# vc8.net
KiCad netlist of a schematic drawn in EAGLE
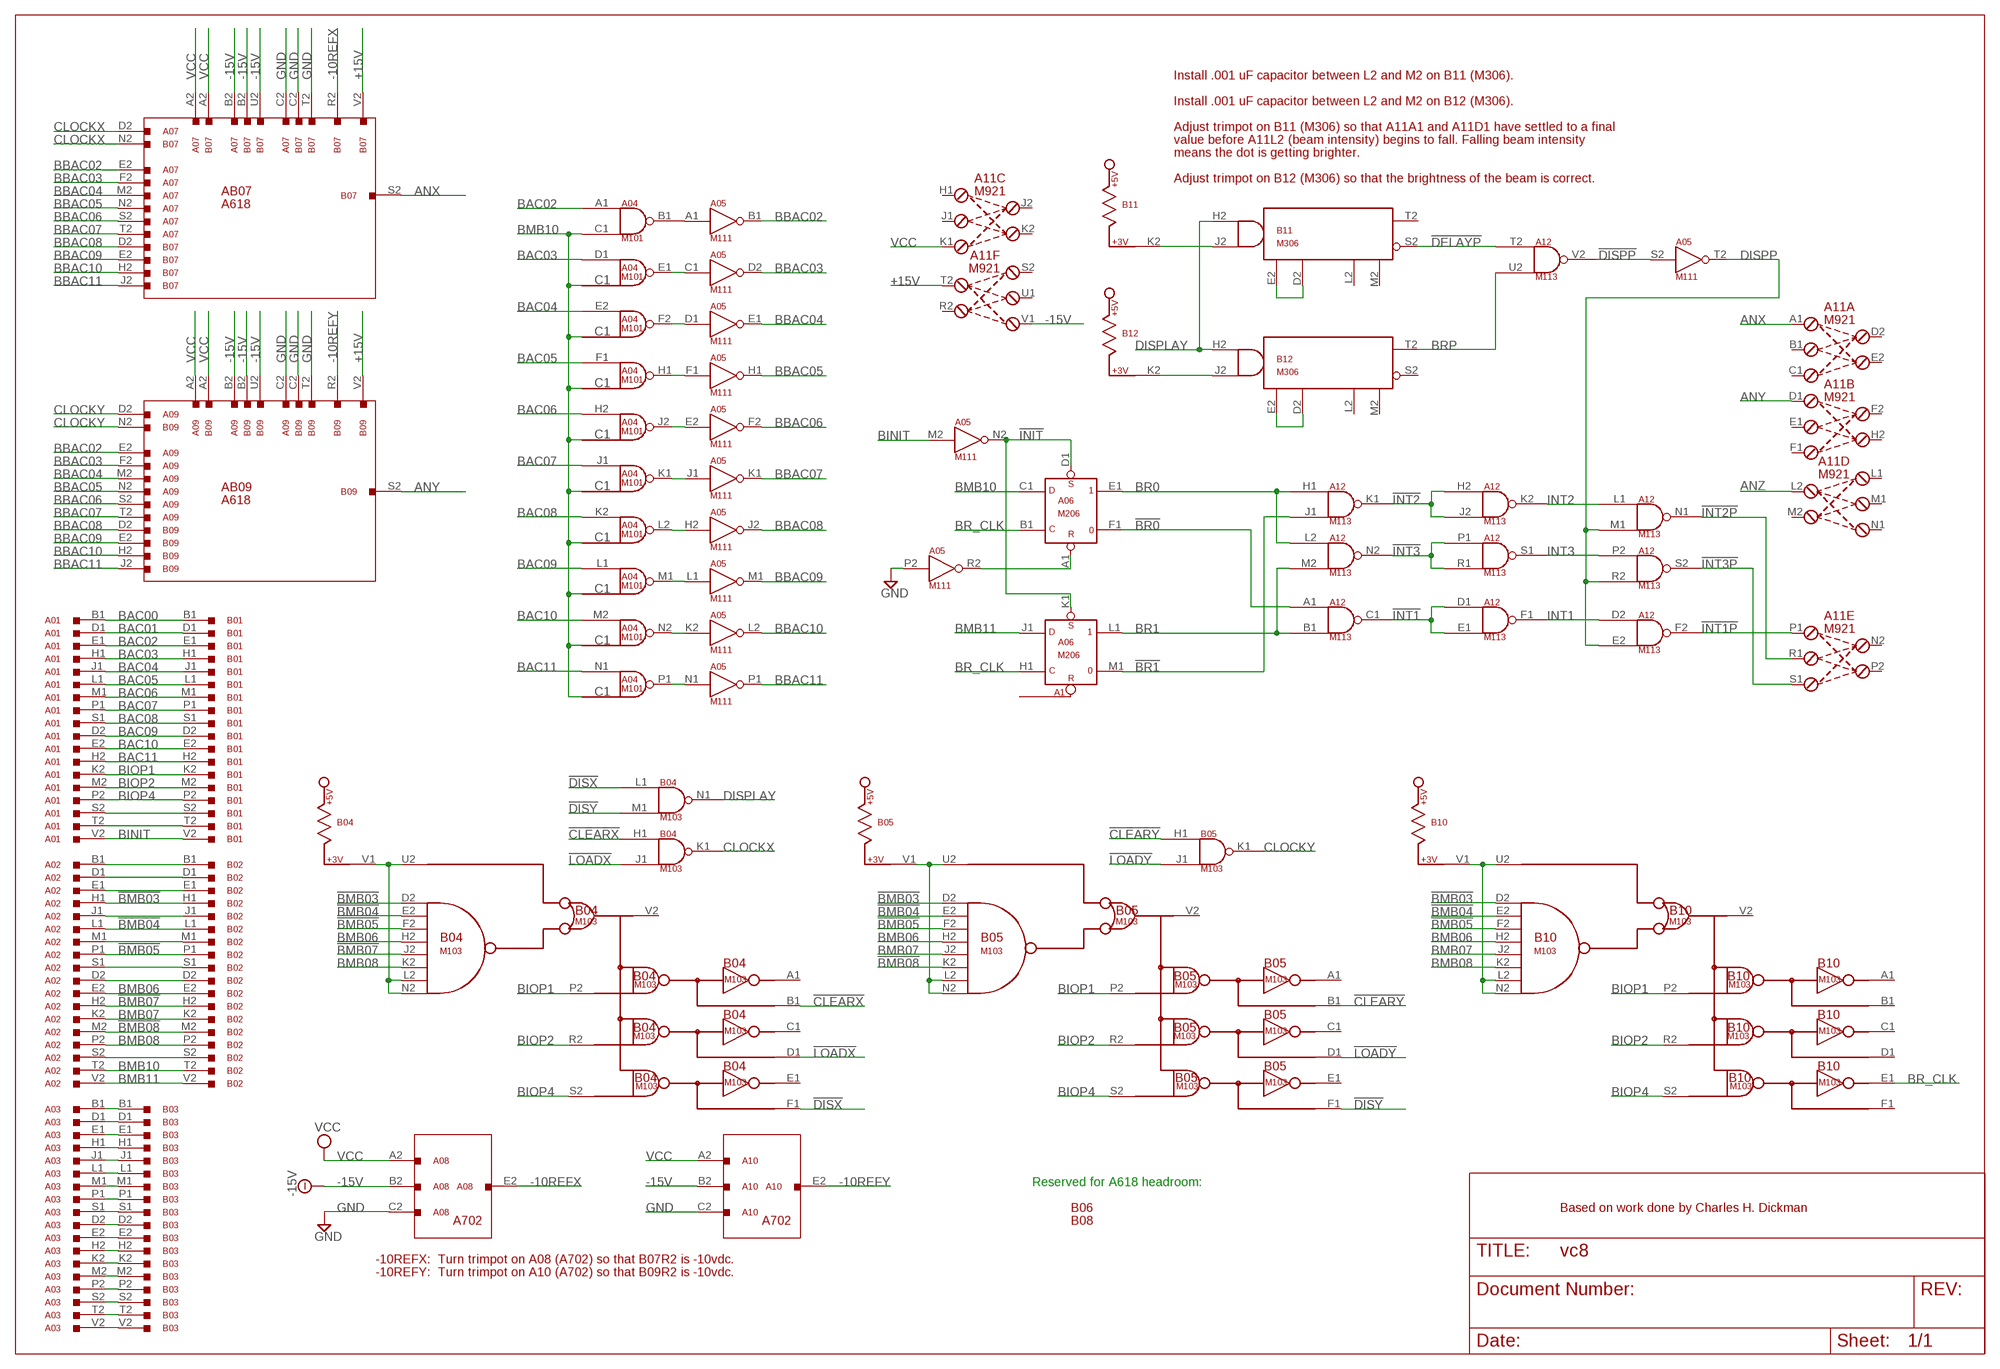
[diagram p0: schematic, sheet 1]

(export (version "E")
  (design (tool "Eeschema 10.0.6"))
  (components
    (comp (ref "A01")
      (value "M903")
      (footprint "eagle-import:H807")
      (libsource (lib "eagle-import") (part "M903"))
    )
    (comp (ref "A02")
      (value "M903")
      (footprint "eagle-import:H807")
      (libsource (lib "eagle-import") (part "M903"))
    )
    (comp (ref "A03")
      (value "M903")
      (footprint "eagle-import:H807")
      (libsource (lib "eagle-import") (part "M903"))
    )
    (comp (ref "A04")
      (value "M101")
      (footprint "eagle-import:H807")
      (libsource (lib "eagle-import") (part "M101"))
    )
    (comp (ref "A05")
      (value "M111")
      (footprint "eagle-import:H807")
      (libsource (lib "eagle-import") (part "M111"))
    )
    (comp (ref "A06")
      (value "M206")
      (footprint "eagle-import:H807")
      (libsource (lib "eagle-import") (part "M206X"))
    )
    (comp (ref "A07")
      (value "A618A")
      (footprint "eagle-import:H807")
      (libsource (lib "eagle-import") (part "M916"))
    )
    (comp (ref "A08")
      (value "A702")
      (footprint "eagle-import:H807")
      (libsource (lib "eagle-import") (part "M916"))
    )
    (comp (ref "A09")
      (value "A618A")
      (footprint "eagle-import:H807")
      (libsource (lib "eagle-import") (part "M916"))
    )
    (comp (ref "A10")
      (value "A702")
      (footprint "eagle-import:H807")
      (libsource (lib "eagle-import") (part "M916"))
    )
    (comp (ref "A11")
      (value "M921")
      (footprint "eagle-import:H807")
      (libsource (lib "eagle-import") (part "M921"))
    )
    (comp (ref "A12")
      (value "M113")
      (footprint "eagle-import:H807")
      (libsource (lib "eagle-import") (part "M113"))
    )
    (comp (ref "B01")
      (value "M903")
      (footprint "eagle-import:H807")
      (libsource (lib "eagle-import") (part "M903"))
    )
    (comp (ref "B02")
      (value "M903")
      (footprint "eagle-import:H807")
      (libsource (lib "eagle-import") (part "M903"))
    )
    (comp (ref "B03")
      (value "M903")
      (footprint "eagle-import:H807")
      (libsource (lib "eagle-import") (part "M903"))
    )
    (comp (ref "B04")
      (value "M103")
      (footprint "eagle-import:H807")
      (libsource (lib "eagle-import") (part "M103"))
    )
    (comp (ref "B05")
      (value "M103")
      (footprint "eagle-import:H807")
      (libsource (lib "eagle-import") (part "M103"))
    )
    (comp (ref "B06")
      (value "EMPTY")
      (footprint "eagle-import:H807")
      (libsource (lib "eagle-import") (part "EMPTY"))
    )
    (comp (ref "B07")
      (value "A618B")
      (footprint "eagle-import:H807")
      (libsource (lib "eagle-import") (part "M916"))
    )
    (comp (ref "B08")
      (value "EMPTY")
      (footprint "eagle-import:H807")
      (libsource (lib "eagle-import") (part "EMPTY"))
    )
    (comp (ref "B09")
      (value "A618B")
      (footprint "eagle-import:H807")
      (libsource (lib "eagle-import") (part "M916"))
    )
    (comp (ref "B10")
      (value "M103")
      (footprint "eagle-import:H807")
      (libsource (lib "eagle-import") (part "M103"))
    )
    (comp (ref "B11")
      (value "M306")
      (footprint "eagle-import:H807")
      (libsource (lib "eagle-import") (part "M306"))
    )
    (comp (ref "B12")
      (value "M306")
      (footprint "eagle-import:H807")
      (libsource (lib "eagle-import") (part "M306"))
    )
  )
  (nets
    (net (code "1") (name "-15V") (class "Default")
      (node (ref "A07") (pin "B2") (pinfunction "P$2_B2") (pintype "bidirectional"))
      (node (ref "A08") (pin "B2") (pinfunction "P$2_B2") (pintype "bidirectional"))
      (node (ref "A09") (pin "B2") (pinfunction "P$2_B2") (pintype "bidirectional"))
      (node (ref "A10") (pin "B2") (pinfunction "P$2_B2") (pintype "bidirectional"))
      (node (ref "A11") (pin "V1") (pinfunction "L3_V1") (pintype "bidirectional"))
      (node (ref "B07") (pin "B2") (pinfunction "P$2_B2") (pintype "bidirectional"))
      (node (ref "B07") (pin "U2") (pinfunction "P$2_U2") (pintype "bidirectional"))
      (node (ref "B09") (pin "B2") (pinfunction "P$2_B2") (pintype "bidirectional"))
      (node (ref "B09") (pin "U2") (pinfunction "P$2_U2") (pintype "bidirectional"))
    )
    (net (code "2") (name "/+15V") (class "Default")
      (node (ref "A11") (pin "T2") (pinfunction "R1_T2") (pintype "bidirectional"))
      (node (ref "B07") (pin "V2") (pinfunction "P$2_V2") (pintype "bidirectional"))
      (node (ref "B09") (pin "V2") (pinfunction "P$2_V2") (pintype "bidirectional"))
    )
    (net (code "3") (name "/-10REFX") (class "Default")
      (node (ref "A08") (pin "E2") (pinfunction "P$2_E2") (pintype "bidirectional"))
      (node (ref "B07") (pin "R2") (pinfunction "P$2_R2") (pintype "bidirectional"))
    )
    (net (code "4") (name "/-10REFY") (class "Default")
      (node (ref "A10") (pin "E2") (pinfunction "P$2_E2") (pintype "bidirectional"))
      (node (ref "B09") (pin "R2") (pinfunction "P$2_R2") (pintype "bidirectional"))
    )
    (net (code "5") (name "/ANX") (class "Default")
      (node (ref "A11") (pin "A1") (pinfunction "L1_A1") (pintype "bidirectional"))
      (node (ref "B07") (pin "S2") (pinfunction "P$2_S2") (pintype "bidirectional"))
    )
    (net (code "6") (name "/ANY") (class "Default")
      (node (ref "A11") (pin "D1") (pinfunction "L1_D1") (pintype "bidirectional"))
      (node (ref "B09") (pin "S2") (pinfunction "P$2_S2") (pintype "bidirectional"))
    )
    (net (code "7") (name "/ANZ") (class "Default")
      (node (ref "A11") (pin "L2") (pinfunction "R1_L2") (pintype "bidirectional"))
    )
    (net (code "8") (name "/BAC00") (class "Default")
      (node (ref "A01") (pin "B1") (pinfunction "P$2_B1") (pintype "bidirectional"))
      (node (ref "B01") (pin "B1") (pinfunction "P$2_B1") (pintype "bidirectional"))
    )
    (net (code "9") (name "/BAC01") (class "Default")
      (node (ref "A01") (pin "D1") (pinfunction "P$2_D1") (pintype "bidirectional"))
      (node (ref "B01") (pin "D1") (pinfunction "P$2_D1") (pintype "bidirectional"))
    )
    (net (code "10") (name "/BAC02") (class "Default")
      (node (ref "A01") (pin "E1") (pinfunction "P$2_E1") (pintype "bidirectional"))
      (node (ref "A04") (pin "A1") (pinfunction "IN1_A1") (pintype "input"))
      (node (ref "B01") (pin "E1") (pinfunction "P$2_E1") (pintype "bidirectional"))
    )
    (net (code "11") (name "/BAC03") (class "Default")
      (node (ref "A01") (pin "H1") (pinfunction "P$2_H1") (pintype "bidirectional"))
      (node (ref "A04") (pin "D1") (pinfunction "IN_D1") (pintype "input"))
      (node (ref "B01") (pin "H1") (pinfunction "P$2_H1") (pintype "bidirectional"))
    )
    (net (code "12") (name "/BAC04") (class "Default")
      (node (ref "A01") (pin "J1") (pinfunction "P$2_J1") (pintype "bidirectional"))
      (node (ref "A04") (pin "E2") (pinfunction "IN_E2") (pintype "input"))
      (node (ref "B01") (pin "J1") (pinfunction "P$2_J1") (pintype "bidirectional"))
    )
    (net (code "13") (name "/BAC05") (class "Default")
      (node (ref "A01") (pin "L1") (pinfunction "P$2_L1") (pintype "bidirectional"))
      (node (ref "A04") (pin "F1") (pinfunction "IN_F1") (pintype "input"))
      (node (ref "B01") (pin "L1") (pinfunction "P$2_L1") (pintype "bidirectional"))
    )
    (net (code "14") (name "/BAC06") (class "Default")
      (node (ref "A01") (pin "M1") (pinfunction "P$2_M1") (pintype "bidirectional"))
      (node (ref "A04") (pin "H2") (pinfunction "IN_H2") (pintype "input"))
      (node (ref "B01") (pin "M1") (pinfunction "P$2_M1") (pintype "bidirectional"))
    )
    (net (code "15") (name "/BAC07") (class "Default")
      (node (ref "A01") (pin "P1") (pinfunction "P$2_P1") (pintype "bidirectional"))
      (node (ref "A04") (pin "J1") (pinfunction "IN_J1") (pintype "input"))
      (node (ref "B01") (pin "P1") (pinfunction "P$2_P1") (pintype "bidirectional"))
    )
    (net (code "16") (name "/BAC08") (class "Default")
      (node (ref "A01") (pin "S1") (pinfunction "P$2_S1") (pintype "bidirectional"))
      (node (ref "A04") (pin "K2") (pinfunction "IN_K2") (pintype "input"))
      (node (ref "B01") (pin "S1") (pinfunction "P$2_S1") (pintype "bidirectional"))
    )
    (net (code "17") (name "/BAC09") (class "Default")
      (node (ref "A01") (pin "D2") (pinfunction "P$2_D2") (pintype "bidirectional"))
      (node (ref "A04") (pin "L1") (pinfunction "IN_L1") (pintype "input"))
      (node (ref "B01") (pin "D2") (pinfunction "P$2_D2") (pintype "bidirectional"))
    )
    (net (code "18") (name "/BAC10") (class "Default")
      (node (ref "A01") (pin "E2") (pinfunction "P$2_E2") (pintype "bidirectional"))
      (node (ref "A04") (pin "M2") (pinfunction "IN_M2") (pintype "input"))
      (node (ref "B01") (pin "E2") (pinfunction "P$2_E2") (pintype "bidirectional"))
    )
    (net (code "19") (name "/BAC11") (class "Default")
      (node (ref "A01") (pin "H2") (pinfunction "P$2_H2") (pintype "bidirectional"))
      (node (ref "A04") (pin "N1") (pinfunction "IN_N1") (pintype "input"))
      (node (ref "B01") (pin "H2") (pinfunction "P$2_H2") (pintype "bidirectional"))
    )
    (net (code "20") (name "/BBAC02") (class "Default")
      (node (ref "A05") (pin "B1") (pinfunction "OUT_B1") (pintype "output"))
      (node (ref "A07") (pin "E2") (pinfunction "P$2_E2") (pintype "bidirectional"))
      (node (ref "A09") (pin "E2") (pinfunction "P$2_E2") (pintype "bidirectional"))
    )
    (net (code "21") (name "/BBAC03") (class "Default")
      (node (ref "A05") (pin "D2") (pinfunction "OUT_D2") (pintype "output"))
      (node (ref "A07") (pin "F2") (pinfunction "P$2_F2") (pintype "bidirectional"))
      (node (ref "A09") (pin "F2") (pinfunction "P$2_F2") (pintype "bidirectional"))
    )
    (net (code "22") (name "/BBAC04") (class "Default")
      (node (ref "A05") (pin "E1") (pinfunction "OUT_E1") (pintype "output"))
      (node (ref "A07") (pin "M2") (pinfunction "P$2_M2") (pintype "bidirectional"))
      (node (ref "A09") (pin "M2") (pinfunction "P$2_M2") (pintype "bidirectional"))
    )
    (net (code "23") (name "/BBAC05") (class "Default")
      (node (ref "A05") (pin "H1") (pinfunction "OUT_H1") (pintype "output"))
      (node (ref "A07") (pin "N2") (pinfunction "P$2_N2") (pintype "bidirectional"))
      (node (ref "A09") (pin "N2") (pinfunction "P$2_N2") (pintype "bidirectional"))
    )
    (net (code "24") (name "/BBAC06") (class "Default")
      (node (ref "A05") (pin "F2") (pinfunction "OUT_F2") (pintype "output"))
      (node (ref "A07") (pin "S2") (pinfunction "P$2_S2") (pintype "bidirectional"))
      (node (ref "A09") (pin "S2") (pinfunction "P$2_S2") (pintype "bidirectional"))
    )
    (net (code "25") (name "/BBAC07") (class "Default")
      (node (ref "A05") (pin "K1") (pinfunction "OUT_K1") (pintype "output"))
      (node (ref "A07") (pin "T2") (pinfunction "P$2_T2") (pintype "bidirectional"))
      (node (ref "A09") (pin "T2") (pinfunction "P$2_T2") (pintype "bidirectional"))
    )
    (net (code "26") (name "/BBAC08") (class "Default")
      (node (ref "A05") (pin "J2") (pinfunction "OUT_J2") (pintype "output"))
      (node (ref "B07") (pin "D2") (pinfunction "P$2_D2") (pintype "bidirectional"))
      (node (ref "B09") (pin "D2") (pinfunction "P$2_D2") (pintype "bidirectional"))
    )
    (net (code "27") (name "/BBAC09") (class "Default")
      (node (ref "A05") (pin "M1") (pinfunction "OUT_M1") (pintype "output"))
      (node (ref "B07") (pin "E2") (pinfunction "P$2_E2") (pintype "bidirectional"))
      (node (ref "B09") (pin "E2") (pinfunction "P$2_E2") (pintype "bidirectional"))
    )
    (net (code "28") (name "/BBAC10") (class "Default")
      (node (ref "A05") (pin "L2") (pinfunction "OUT_L2") (pintype "output"))
      (node (ref "B07") (pin "H2") (pinfunction "P$2_H2") (pintype "bidirectional"))
      (node (ref "B09") (pin "H2") (pinfunction "P$2_H2") (pintype "bidirectional"))
    )
    (net (code "29") (name "/BBAC11") (class "Default")
      (node (ref "A05") (pin "P1") (pinfunction "OUT_P1") (pintype "output"))
      (node (ref "B07") (pin "J2") (pinfunction "P$2_J2") (pintype "bidirectional"))
      (node (ref "B09") (pin "J2") (pinfunction "P$2_J2") (pintype "bidirectional"))
    )
    (net (code "30") (name "/BINIT") (class "Default")
      (node (ref "A01") (pin "V2") (pinfunction "P$2_V2") (pintype "bidirectional"))
      (node (ref "A05") (pin "M2") (pinfunction "IN_M2") (pintype "input"))
      (node (ref "B01") (pin "V2") (pinfunction "P$2_V2") (pintype "bidirectional"))
    )
    (net (code "31") (name "/BIOP1") (class "Default")
      (node (ref "A01") (pin "K2") (pinfunction "P$2_K2") (pintype "bidirectional"))
      (node (ref "B01") (pin "K2") (pinfunction "P$2_K2") (pintype "bidirectional"))
      (node (ref "B04") (pin "P2") (pinfunction "P2_P2") (pintype "input"))
      (node (ref "B05") (pin "P2") (pinfunction "P2_P2") (pintype "input"))
      (node (ref "B10") (pin "P2") (pinfunction "P2_P2") (pintype "input"))
    )
    (net (code "32") (name "/BIOP2") (class "Default")
      (node (ref "A01") (pin "M2") (pinfunction "P$2_M2") (pintype "bidirectional"))
      (node (ref "B01") (pin "M2") (pinfunction "P$2_M2") (pintype "bidirectional"))
      (node (ref "B04") (pin "R2") (pinfunction "R2_R2") (pintype "input"))
      (node (ref "B05") (pin "R2") (pinfunction "R2_R2") (pintype "input"))
      (node (ref "B10") (pin "R2") (pinfunction "R2_R2") (pintype "input"))
    )
    (net (code "33") (name "/BIOP4") (class "Default")
      (node (ref "A01") (pin "P2") (pinfunction "P$2_P2") (pintype "bidirectional"))
      (node (ref "B01") (pin "P2") (pinfunction "P$2_P2") (pintype "bidirectional"))
      (node (ref "B04") (pin "S2") (pinfunction "S2_S2") (pintype "input"))
      (node (ref "B05") (pin "S2") (pinfunction "S2_S2") (pintype "input"))
      (node (ref "B10") (pin "S2") (pinfunction "S2_S2") (pintype "input"))
    )
    (net (code "34") (name "/BMB06") (class "Default")
      (node (ref "A02") (pin "E2") (pinfunction "P$2_E2") (pintype "bidirectional"))
      (node (ref "B02") (pin "E2") (pinfunction "P$2_E2") (pintype "bidirectional"))
      (node (ref "B04") (pin "H2") (pinfunction "H2_H2") (pintype "input"))
      (node (ref "B05") (pin "H2") (pinfunction "H2_H2") (pintype "input"))
      (node (ref "B10") (pin "H2") (pinfunction "H2_H2") (pintype "input"))
    )
    (net (code "35") (name "/BMB07") (class "Default")
      (node (ref "A02") (pin "K2") (pinfunction "P$2_K2") (pintype "bidirectional"))
      (node (ref "B02") (pin "K2") (pinfunction "P$2_K2") (pintype "bidirectional"))
      (node (ref "B05") (pin "J2") (pinfunction "J2_J2") (pintype "input"))
      (node (ref "B10") (pin "J2") (pinfunction "J2_J2") (pintype "input"))
    )
    (net (code "36") (name "/BMB08") (class "Default")
      (node (ref "A02") (pin "P2") (pinfunction "P$2_P2") (pintype "bidirectional"))
      (node (ref "B02") (pin "P2") (pinfunction "P$2_P2") (pintype "bidirectional"))
      (node (ref "B04") (pin "K2") (pinfunction "K2_K2") (pintype "input"))
      (node (ref "B10") (pin "K2") (pinfunction "K2_K2") (pintype "input"))
    )
    (net (code "37") (name "/BMB10") (class "Default")
      (node (ref "A02") (pin "T2") (pinfunction "P$2_T2") (pintype "bidirectional"))
      (node (ref "A04") (pin "C1") (pinfunction "IN2_C1") (pintype "input"))
      (node (ref "A06") (pin "C1") (pinfunction "D_C1") (pintype "input"))
      (node (ref "B02") (pin "T2") (pinfunction "P$2_T2") (pintype "bidirectional"))
    )
    (net (code "38") (name "/BMB11") (class "Default")
      (node (ref "A02") (pin "V2") (pinfunction "P$2_V2") (pintype "bidirectional"))
      (node (ref "A06") (pin "J1") (pinfunction "D_J1") (pintype "input"))
      (node (ref "B02") (pin "V2") (pinfunction "P$2_V2") (pintype "bidirectional"))
    )
    (net (code "39") (name "/BR0") (class "Default")
      (node (ref "A06") (pin "E1") (pinfunction "1_E1") (pintype "output"))
      (node (ref "A12") (pin "H1") (pinfunction "IN1_H1") (pintype "input"))
      (node (ref "A12") (pin "L2") (pinfunction "IN1_L2") (pintype "input"))
    )
    (net (code "40") (name "/BR1") (class "Default")
      (node (ref "A06") (pin "L1") (pinfunction "1_L1") (pintype "output"))
      (node (ref "A12") (pin "B1") (pinfunction "IN2_B1") (pintype "input"))
      (node (ref "A12") (pin "M2") (pinfunction "IN2_M2") (pintype "input"))
    )
    (net (code "41") (name "/BRP") (class "Default")
      (node (ref "A12") (pin "U2") (pinfunction "IN2_U2") (pintype "input"))
      (node (ref "B12") (pin "T2") (pinfunction "T_T2") (pintype "output"))
    )
    (net (code "42") (name "/BR_CLK") (class "Default")
      (node (ref "A06") (pin "B1") (pinfunction "C_B1") (pintype "input"))
      (node (ref "A06") (pin "H1") (pinfunction "C_H1") (pintype "input"))
      (node (ref "B10") (pin "E1") (pinfunction "E1_E1") (pintype "output"))
    )
    (net (code "43") (name "/CLOCKX") (class "Default")
      (node (ref "A07") (pin "D2") (pinfunction "P$2_D2") (pintype "bidirectional"))
      (node (ref "B04") (pin "K1") (pinfunction "OUT_K1") (pintype "output"))
      (node (ref "B07") (pin "N2") (pinfunction "P$2_N2") (pintype "bidirectional"))
    )
    (net (code "44") (name "/CLOCKY") (class "Default")
      (node (ref "A09") (pin "D2") (pinfunction "P$2_D2") (pintype "bidirectional"))
      (node (ref "B05") (pin "K1") (pinfunction "OUT_K1") (pintype "output"))
      (node (ref "B09") (pin "N2") (pinfunction "P$2_N2") (pintype "bidirectional"))
    )
    (net (code "45") (name "/DISPLAY") (class "Default")
      (node (ref "B04") (pin "N1") (pinfunction "OUT_N1") (pintype "output"))
      (node (ref "B11") (pin "H2") (pinfunction "H_H2") (pintype "input"))
      (node (ref "B12") (pin "H2") (pinfunction "H_H2") (pintype "input"))
    )
    (net (code "46") (name "/DISPP") (class "Default")
      (node (ref "A05") (pin "T2") (pinfunction "OUT_T2") (pintype "output"))
      (node (ref "A12") (pin "E2") (pinfunction "IN2_E2") (pintype "input"))
      (node (ref "A12") (pin "M1") (pinfunction "IN2_M1") (pintype "input"))
      (node (ref "A12") (pin "R2") (pinfunction "IN2_R2") (pintype "input"))
    )
    (net (code "47") (name "/INT1") (class "Default")
      (node (ref "A12") (pin "D2") (pinfunction "IN1_D2") (pintype "input"))
      (node (ref "A12") (pin "F1") (pinfunction "OUT_F1") (pintype "output"))
    )
    (net (code "48") (name "/INT2") (class "Default")
      (node (ref "A12") (pin "K2") (pinfunction "OUT_K2") (pintype "output"))
      (node (ref "A12") (pin "L1") (pinfunction "IN1_L1") (pintype "input"))
    )
    (net (code "49") (name "/INT3") (class "Default")
      (node (ref "A12") (pin "P2") (pinfunction "IN1_P2") (pintype "input"))
      (node (ref "A12") (pin "S1") (pinfunction "OUT_S1") (pintype "output"))
    )
    (net (code "50") (name "/~{BMB03}") (class "Default")
      (node (ref "A02") (pin "H1") (pinfunction "P$2_H1") (pintype "bidirectional"))
      (node (ref "B02") (pin "H1") (pinfunction "P$2_H1") (pintype "bidirectional"))
      (node (ref "B04") (pin "D2") (pinfunction "D2_D2") (pintype "input"))
      (node (ref "B05") (pin "D2") (pinfunction "D2_D2") (pintype "input"))
      (node (ref "B10") (pin "D2") (pinfunction "D2_D2") (pintype "input"))
    )
    (net (code "51") (name "/~{BMB04}") (class "Default")
      (node (ref "A02") (pin "L1") (pinfunction "P$2_L1") (pintype "bidirectional"))
      (node (ref "B02") (pin "L1") (pinfunction "P$2_L1") (pintype "bidirectional"))
      (node (ref "B04") (pin "E2") (pinfunction "E2_E2") (pintype "input"))
      (node (ref "B05") (pin "E2") (pinfunction "E2_E2") (pintype "input"))
      (node (ref "B10") (pin "E2") (pinfunction "E2_E2") (pintype "input"))
    )
    (net (code "52") (name "/~{BMB05}") (class "Default")
      (node (ref "A02") (pin "P1") (pinfunction "P$2_P1") (pintype "bidirectional"))
      (node (ref "B02") (pin "P1") (pinfunction "P$2_P1") (pintype "bidirectional"))
      (node (ref "B04") (pin "F2") (pinfunction "F2_F2") (pintype "input"))
      (node (ref "B05") (pin "F2") (pinfunction "F2_F2") (pintype "input"))
      (node (ref "B10") (pin "F2") (pinfunction "F2_F2") (pintype "input"))
    )
    (net (code "53") (name "/~{BMB07}") (class "Default")
      (node (ref "A02") (pin "H2") (pinfunction "P$2_H2") (pintype "bidirectional"))
      (node (ref "B02") (pin "H2") (pinfunction "P$2_H2") (pintype "bidirectional"))
      (node (ref "B04") (pin "J2") (pinfunction "J2_J2") (pintype "input"))
    )
    (net (code "54") (name "/~{BMB08}") (class "Default")
      (node (ref "A02") (pin "M2") (pinfunction "P$2_M2") (pintype "bidirectional"))
      (node (ref "B02") (pin "M2") (pinfunction "P$2_M2") (pintype "bidirectional"))
      (node (ref "B05") (pin "K2") (pinfunction "K2_K2") (pintype "input"))
    )
    (net (code "55") (name "/~{BR0}") (class "Default")
      (node (ref "A06") (pin "F1") (pinfunction "0_F1") (pintype "output"))
      (node (ref "A12") (pin "A1") (pinfunction "IN1_A1") (pintype "input"))
    )
    (net (code "56") (name "/~{BR1}") (class "Default")
      (node (ref "A06") (pin "M1") (pinfunction "0_M1") (pintype "output"))
      (node (ref "A12") (pin "J1") (pinfunction "IN2_J1") (pintype "input"))
    )
    (net (code "57") (name "/~{CLEARX}") (class "Default")
      (node (ref "B04") (pin "B1") (pinfunction "B1_B1") (pintype "output"))
      (node (ref "B04") (pin "H1") (pinfunction "IN1_H1") (pintype "input"))
    )
    (net (code "58") (name "/~{CLEARY}") (class "Default")
      (node (ref "B05") (pin "B1") (pinfunction "B1_B1") (pintype "output"))
      (node (ref "B05") (pin "H1") (pinfunction "IN1_H1") (pintype "input"))
    )
    (net (code "59") (name "/~{DELAYP}") (class "Default")
      (node (ref "A12") (pin "T2") (pinfunction "IN1_T2") (pintype "input"))
      (node (ref "B11") (pin "S2") (pinfunction "S_S2") (pintype "output"))
    )
    (net (code "60") (name "/~{DISPP}") (class "Default")
      (node (ref "A05") (pin "S2") (pinfunction "IN_S2") (pintype "input"))
      (node (ref "A12") (pin "V2") (pinfunction "OUT_V2") (pintype "output"))
    )
    (net (code "61") (name "/~{DISX}") (class "Default")
      (node (ref "B04") (pin "F1") (pinfunction "F1_F1") (pintype "output"))
      (node (ref "B04") (pin "L1") (pinfunction "IN1_L1") (pintype "input"))
    )
    (net (code "62") (name "/~{DISY}") (class "Default")
      (node (ref "B04") (pin "M1") (pinfunction "IN2_M1") (pintype "input"))
      (node (ref "B05") (pin "F1") (pinfunction "F1_F1") (pintype "output"))
    )
    (net (code "63") (name "/~{INIT}") (class "Default")
      (node (ref "A05") (pin "N2") (pinfunction "OUT_N2") (pintype "output"))
      (node (ref "A06") (pin "D1") (pinfunction "S_D1") (pintype "input"))
      (node (ref "A06") (pin "K1") (pinfunction "S_K1") (pintype "input"))
    )
    (net (code "64") (name "/~{INT1P}") (class "Default")
      (node (ref "A11") (pin "P1") (pinfunction "L1_P1") (pintype "bidirectional"))
      (node (ref "A12") (pin "F2") (pinfunction "OUT_F2") (pintype "output"))
    )
    (net (code "65") (name "/~{INT1}") (class "Default")
      (node (ref "A12") (pin "C1") (pinfunction "OUT_C1") (pintype "output"))
      (node (ref "A12") (pin "D1") (pinfunction "IN1_D1") (pintype "input"))
      (node (ref "A12") (pin "E1") (pinfunction "IN2_E1") (pintype "input"))
    )
    (net (code "66") (name "/~{INT2P}") (class "Default")
      (node (ref "A11") (pin "R1") (pinfunction "L2_R1") (pintype "bidirectional"))
      (node (ref "A12") (pin "N1") (pinfunction "OUT_N1") (pintype "output"))
    )
    (net (code "67") (name "/~{INT2}") (class "Default")
      (node (ref "A12") (pin "H2") (pinfunction "IN1_H2") (pintype "input"))
      (node (ref "A12") (pin "J2") (pinfunction "IN2_J2") (pintype "input"))
      (node (ref "A12") (pin "K1") (pinfunction "OUT_K1") (pintype "output"))
    )
    (net (code "68") (name "/~{INT3P}") (class "Default")
      (node (ref "A11") (pin "S1") (pinfunction "L3_S1") (pintype "bidirectional"))
      (node (ref "A12") (pin "S2") (pinfunction "OUT_S2") (pintype "output"))
    )
    (net (code "69") (name "/~{INT3}") (class "Default")
      (node (ref "A12") (pin "N2") (pinfunction "OUT_N2") (pintype "output"))
      (node (ref "A12") (pin "P1") (pinfunction "IN1_P1") (pintype "input"))
      (node (ref "A12") (pin "R1") (pinfunction "IN2_R1") (pintype "input"))
    )
    (net (code "70") (name "/~{LOADX}") (class "Default")
      (node (ref "B04") (pin "D1") (pinfunction "D1_D1") (pintype "output"))
      (node (ref "B04") (pin "J1") (pinfunction "IN2_J1") (pintype "input"))
    )
    (net (code "71") (name "/~{LOADY}") (class "Default")
      (node (ref "B05") (pin "D1") (pinfunction "D1_D1") (pintype "output"))
      (node (ref "B05") (pin "J1") (pinfunction "IN2_J1") (pintype "input"))
    )
    (net (code "72") (name "GND") (class "Default")
      (node (ref "A05") (pin "P2") (pinfunction "IN_P2") (pintype "input"))
      (node (ref "A07") (pin "C2") (pinfunction "P$2_C2") (pintype "bidirectional"))
      (node (ref "A08") (pin "C2") (pinfunction "P$2_C2") (pintype "bidirectional"))
      (node (ref "A09") (pin "C2") (pinfunction "P$2_C2") (pintype "bidirectional"))
      (node (ref "A10") (pin "C2") (pinfunction "P$2_C2") (pintype "bidirectional"))
      (node (ref "B07") (pin "C2") (pinfunction "P$2_C2") (pintype "bidirectional"))
      (node (ref "B07") (pin "T2") (pinfunction "P$2_T2") (pintype "bidirectional"))
      (node (ref "B09") (pin "C2") (pinfunction "P$2_C2") (pintype "bidirectional"))
      (node (ref "B09") (pin "T2") (pinfunction "P$2_T2") (pintype "bidirectional"))
    )
    (net (code "73") (name "Net-(A01AB-P$2)") (class "Default")
      (node (ref "A01") (pin "S2") (pinfunction "P$2_S2") (pintype "bidirectional"))
      (node (ref "B01") (pin "S2") (pinfunction "P$2_S2") (pintype "bidirectional"))
    )
    (net (code "74") (name "Net-(A01AD-P$2)") (class "Default")
      (node (ref "A01") (pin "T2") (pinfunction "P$2_T2") (pintype "bidirectional"))
      (node (ref "B01") (pin "T2") (pinfunction "P$2_T2") (pintype "bidirectional"))
    )
    (net (code "75") (name "Net-(A02AA-P$2)") (class "Default")
      (node (ref "A02") (pin "S1") (pinfunction "P$2_S1") (pintype "bidirectional"))
      (node (ref "B02") (pin "S1") (pinfunction "P$2_S1") (pintype "bidirectional"))
    )
    (net (code "76") (name "Net-(A02AB-P$2)") (class "Default")
      (node (ref "A02") (pin "S2") (pinfunction "P$2_S2") (pintype "bidirectional"))
      (node (ref "B02") (pin "S2") (pinfunction "P$2_S2") (pintype "bidirectional"))
    )
    (net (code "77") (name "Net-(A02B-P$2)") (class "Default")
      (node (ref "A02") (pin "B1") (pinfunction "P$2_B1") (pintype "bidirectional"))
      (node (ref "B02") (pin "B1") (pinfunction "P$2_B1") (pintype "bidirectional"))
    )
    (net (code "78") (name "Net-(A02E-P$2)") (class "Default")
      (node (ref "A02") (pin "D1") (pinfunction "P$2_D1") (pintype "bidirectional"))
      (node (ref "B02") (pin "D1") (pinfunction "P$2_D1") (pintype "bidirectional"))
    )
    (net (code "79") (name "Net-(A02F-P$2)") (class "Default")
      (node (ref "A02") (pin "D2") (pinfunction "P$2_D2") (pintype "bidirectional"))
      (node (ref "B02") (pin "D2") (pinfunction "P$2_D2") (pintype "bidirectional"))
    )
    (net (code "80") (name "Net-(A02G-P$2)") (class "Default")
      (node (ref "A02") (pin "E1") (pinfunction "P$2_E1") (pintype "bidirectional"))
      (node (ref "B02") (pin "E1") (pinfunction "P$2_E1") (pintype "bidirectional"))
    )
    (net (code "81") (name "Net-(A02M-P$2)") (class "Default")
      (node (ref "A02") (pin "J1") (pinfunction "P$2_J1") (pintype "bidirectional"))
      (node (ref "B02") (pin "J1") (pinfunction "P$2_J1") (pintype "bidirectional"))
    )
    (net (code "82") (name "Net-(A02S-P$2)") (class "Default")
      (node (ref "A02") (pin "M1") (pinfunction "P$2_M1") (pintype "bidirectional"))
      (node (ref "B02") (pin "M1") (pinfunction "P$2_M1") (pintype "bidirectional"))
    )
    (net (code "83") (name "Net-(A03AA-P$2)") (class "Default")
      (node (ref "A03") (pin "S1") (pinfunction "P$2_S1") (pintype "bidirectional"))
      (node (ref "B03") (pin "S1") (pinfunction "P$2_S1") (pintype "bidirectional"))
    )
    (net (code "84") (name "Net-(A03AB-P$2)") (class "Default")
      (node (ref "A03") (pin "S2") (pinfunction "P$2_S2") (pintype "bidirectional"))
      (node (ref "B03") (pin "S2") (pinfunction "P$2_S2") (pintype "bidirectional"))
    )
    (net (code "85") (name "Net-(A03AD-P$2)") (class "Default")
      (node (ref "A03") (pin "T2") (pinfunction "P$2_T2") (pintype "bidirectional"))
      (node (ref "B03") (pin "T2") (pinfunction "P$2_T2") (pintype "bidirectional"))
    )
    (net (code "86") (name "Net-(A03AF-P$2)") (class "Default")
      (node (ref "A03") (pin "V2") (pinfunction "P$2_V2") (pintype "bidirectional"))
      (node (ref "B03") (pin "V2") (pinfunction "P$2_V2") (pintype "bidirectional"))
    )
    (net (code "87") (name "Net-(A03B-P$2)") (class "Default")
      (node (ref "A03") (pin "B1") (pinfunction "P$2_B1") (pintype "bidirectional"))
      (node (ref "B03") (pin "B1") (pinfunction "P$2_B1") (pintype "bidirectional"))
    )
    (net (code "88") (name "Net-(A03E-P$2)") (class "Default")
      (node (ref "A03") (pin "D1") (pinfunction "P$2_D1") (pintype "bidirectional"))
      (node (ref "B03") (pin "D1") (pinfunction "P$2_D1") (pintype "bidirectional"))
    )
    (net (code "89") (name "Net-(A03F-P$2)") (class "Default")
      (node (ref "A03") (pin "D2") (pinfunction "P$2_D2") (pintype "bidirectional"))
      (node (ref "B03") (pin "D2") (pinfunction "P$2_D2") (pintype "bidirectional"))
    )
    (net (code "90") (name "Net-(A03G-P$2)") (class "Default")
      (node (ref "A03") (pin "E1") (pinfunction "P$2_E1") (pintype "bidirectional"))
      (node (ref "B03") (pin "E1") (pinfunction "P$2_E1") (pintype "bidirectional"))
    )
    (net (code "91") (name "Net-(A03H-P$2)") (class "Default")
      (node (ref "A03") (pin "E2") (pinfunction "P$2_E2") (pintype "bidirectional"))
      (node (ref "B03") (pin "E2") (pinfunction "P$2_E2") (pintype "bidirectional"))
    )
    (net (code "92") (name "Net-(A03K-P$2)") (class "Default")
      (node (ref "A03") (pin "H1") (pinfunction "P$2_H1") (pintype "bidirectional"))
      (node (ref "B03") (pin "H1") (pinfunction "P$2_H1") (pintype "bidirectional"))
    )
    (net (code "93") (name "Net-(A03L-P$2)") (class "Default")
      (node (ref "A03") (pin "H2") (pinfunction "P$2_H2") (pintype "bidirectional"))
      (node (ref "B03") (pin "H2") (pinfunction "P$2_H2") (pintype "bidirectional"))
    )
    (net (code "94") (name "Net-(A03M-P$2)") (class "Default")
      (node (ref "A03") (pin "J1") (pinfunction "P$2_J1") (pintype "bidirectional"))
      (node (ref "B03") (pin "J1") (pinfunction "P$2_J1") (pintype "bidirectional"))
    )
    (net (code "95") (name "Net-(A03P-P$2)") (class "Default")
      (node (ref "A03") (pin "K2") (pinfunction "P$2_K2") (pintype "bidirectional"))
      (node (ref "B03") (pin "K2") (pinfunction "P$2_K2") (pintype "bidirectional"))
    )
    (net (code "96") (name "Net-(A03Q-P$2)") (class "Default")
      (node (ref "A03") (pin "L1") (pinfunction "P$2_L1") (pintype "bidirectional"))
      (node (ref "B03") (pin "L1") (pinfunction "P$2_L1") (pintype "bidirectional"))
    )
    (net (code "97") (name "Net-(A03S-P$2)") (class "Default")
      (node (ref "A03") (pin "M1") (pinfunction "P$2_M1") (pintype "bidirectional"))
      (node (ref "B03") (pin "M1") (pinfunction "P$2_M1") (pintype "bidirectional"))
    )
    (net (code "98") (name "Net-(A03T-P$2)") (class "Default")
      (node (ref "A03") (pin "M2") (pinfunction "P$2_M2") (pintype "bidirectional"))
      (node (ref "B03") (pin "M2") (pinfunction "P$2_M2") (pintype "bidirectional"))
    )
    (net (code "99") (name "Net-(A03W-P$2)") (class "Default")
      (node (ref "A03") (pin "P1") (pinfunction "P$2_P1") (pintype "bidirectional"))
      (node (ref "B03") (pin "P1") (pinfunction "P$2_P1") (pintype "bidirectional"))
    )
    (net (code "100") (name "Net-(A03X-P$2)") (class "Default")
      (node (ref "A03") (pin "P2") (pinfunction "P$2_P2") (pintype "bidirectional"))
      (node (ref "B03") (pin "P2") (pinfunction "P$2_P2") (pintype "bidirectional"))
    )
    (net (code "101") (name "Net-(A04A-OUT)") (class "Default")
      (node (ref "A04") (pin "B1") (pinfunction "OUT_B1") (pintype "output"))
      (node (ref "A05") (pin "A1") (pinfunction "IN_A1") (pintype "input"))
    )
    (net (code "102") (name "Net-(A04B-OUT)") (class "Default")
      (node (ref "A04") (pin "E1") (pinfunction "OUT_E1") (pintype "output"))
      (node (ref "A05") (pin "C1") (pinfunction "IN_C1") (pintype "input"))
    )
    (net (code "103") (name "Net-(A04C-OUT)") (class "Default")
      (node (ref "A04") (pin "F2") (pinfunction "OUT_F2") (pintype "output"))
      (node (ref "A05") (pin "D1") (pinfunction "IN_D1") (pintype "input"))
    )
    (net (code "104") (name "Net-(A04F-OUT)") (class "Default")
      (node (ref "A04") (pin "H1") (pinfunction "OUT_H1") (pintype "output"))
      (node (ref "A05") (pin "F1") (pinfunction "IN_F1") (pintype "input"))
    )
    (net (code "105") (name "Net-(A04G-OUT)") (class "Default")
      (node (ref "A04") (pin "J2") (pinfunction "OUT_J2") (pintype "output"))
      (node (ref "A05") (pin "E2") (pinfunction "IN_E2") (pintype "input"))
    )
    (net (code "106") (name "Net-(A04H-OUT)") (class "Default")
      (node (ref "A04") (pin "K1") (pinfunction "OUT_K1") (pintype "output"))
      (node (ref "A05") (pin "J1") (pinfunction "IN_J1") (pintype "input"))
    )
    (net (code "107") (name "Net-(A04I-OUT)") (class "Default")
      (node (ref "A04") (pin "L2") (pinfunction "OUT_L2") (pintype "output"))
      (node (ref "A05") (pin "H2") (pinfunction "IN_H2") (pintype "input"))
    )
    (net (code "108") (name "Net-(A04J-OUT)") (class "Default")
      (node (ref "A04") (pin "M1") (pinfunction "OUT_M1") (pintype "output"))
      (node (ref "A05") (pin "L1") (pinfunction "IN_L1") (pintype "input"))
    )
    (net (code "109") (name "Net-(A04K-OUT)") (class "Default")
      (node (ref "A04") (pin "N2") (pinfunction "OUT_N2") (pintype "output"))
      (node (ref "A05") (pin "K2") (pinfunction "IN_K2") (pintype "input"))
    )
    (net (code "110") (name "Net-(A04L-OUT)") (class "Default")
      (node (ref "A04") (pin "P1") (pinfunction "OUT_P1") (pintype "output"))
      (node (ref "A05") (pin "N1") (pinfunction "IN_N1") (pintype "input"))
    )
    (net (code "111") (name "Net-(A05N-OUT)") (class "Default")
      (node (ref "A05") (pin "R2") (pinfunction "OUT_R2") (pintype "output"))
      (node (ref "A06") (pin "A1") (pinfunction "R_A1") (pintype "input"))
    )
    (net (code "112") (name "Net-(B04E-P$1)") (class "Default")
      (node (ref "B04") (pin "L2") (pinfunction "L2_L2") (pintype "input"))
      (node (ref "B04") (pin "N2") (pinfunction "N2_N2") (pintype "input"))
      (node (ref "B04") (pin "U2") (pinfunction "U2_U2") (pintype "input"))
      (node (ref "B04") (pin "V1") (pinfunction "P$1_V1") (pintype "passive"))
    )
    (net (code "113") (name "Net-(B05E-P$1)") (class "Default")
      (node (ref "B05") (pin "L2") (pinfunction "L2_L2") (pintype "input"))
      (node (ref "B05") (pin "N2") (pinfunction "N2_N2") (pintype "input"))
      (node (ref "B05") (pin "U2") (pinfunction "U2_U2") (pintype "input"))
      (node (ref "B05") (pin "V1") (pinfunction "P$1_V1") (pintype "passive"))
    )
    (net (code "114") (name "Net-(B10E-P$1)") (class "Default")
      (node (ref "B10") (pin "L2") (pinfunction "L2_L2") (pintype "input"))
      (node (ref "B10") (pin "N2") (pinfunction "N2_N2") (pintype "input"))
      (node (ref "B10") (pin "U2") (pinfunction "U2_U2") (pintype "input"))
      (node (ref "B10") (pin "V1") (pinfunction "P$1_V1") (pintype "passive"))
    )
    (net (code "115") (name "Net-(B11A-D)") (class "Default")
      (node (ref "B11") (pin "D2") (pinfunction "D_D2") (pintype "passive"))
      (node (ref "B11") (pin "E2") (pinfunction "E_E2") (pintype "passive"))
    )
    (net (code "116") (name "Net-(B11A-J)") (class "Default")
      (node (ref "B11") (pin "J2") (pinfunction "J_J2") (pintype "input"))
      (node (ref "B11") (pin "K2") (pinfunction "P$1_K2") (pintype "passive"))
    )
    (net (code "117") (name "Net-(B12A-D)") (class "Default")
      (node (ref "B12") (pin "D2") (pinfunction "D_D2") (pintype "passive"))
      (node (ref "B12") (pin "E2") (pinfunction "E_E2") (pintype "passive"))
    )
    (net (code "118") (name "Net-(B12A-J)") (class "Default")
      (node (ref "B12") (pin "J2") (pinfunction "J_J2") (pintype "input"))
      (node (ref "B12") (pin "K2") (pinfunction "P$1_K2") (pintype "passive"))
    )
    (net (code "119") (name "VCC") (class "Default")
      (node (ref "A07") (pin "A2") (pinfunction "P$2_A2") (pintype "bidirectional"))
      (node (ref "A08") (pin "A2") (pinfunction "P$2_A2") (pintype "bidirectional"))
      (node (ref "A09") (pin "A2") (pinfunction "P$2_A2") (pintype "bidirectional"))
      (node (ref "A10") (pin "A2") (pinfunction "P$2_A2") (pintype "bidirectional"))
      (node (ref "A11") (pin "K1") (pinfunction "L3_K1") (pintype "bidirectional"))
      (node (ref "B07") (pin "A2") (pinfunction "P$2_A2") (pintype "bidirectional"))
      (node (ref "B09") (pin "A2") (pinfunction "P$2_A2") (pintype "bidirectional"))
    )
    (net (code "120") (name "unconnected-(A11-PadL1)") (class "Default")
      (node (ref "A11") (pin "L1") (pinfunction "L1_L1") (pintype "bidirectional"))
    )
    (net (code "121") (name "unconnected-(A11-PadR2)") (class "Default")
      (node (ref "A11") (pin "R2") (pinfunction "R2_R2") (pintype "bidirectional"))
    )
    (net (code "122") (name "unconnected-(A11A-L2-PadB1)") (class "Default")
      (node (ref "A11") (pin "B1") (pinfunction "L2_B1") (pintype "bidirectional"))
    )
    (net (code "123") (name "unconnected-(A11A-L3-PadC1)") (class "Default")
      (node (ref "A11") (pin "C1") (pinfunction "L3_C1") (pintype "bidirectional"))
    )
    (net (code "124") (name "unconnected-(A11A-R1-PadD2)") (class "Default")
      (node (ref "A11") (pin "D2") (pinfunction "R1_D2") (pintype "bidirectional"))
    )
    (net (code "125") (name "unconnected-(A11A-R2-PadE2)") (class "Default")
      (node (ref "A11") (pin "E2") (pinfunction "R2_E2") (pintype "bidirectional"))
    )
    (net (code "126") (name "unconnected-(A11B-L2-PadE1)") (class "Default")
      (node (ref "A11") (pin "E1") (pinfunction "L2_E1") (pintype "bidirectional"))
    )
    (net (code "127") (name "unconnected-(A11B-L3-PadF1)") (class "Default")
      (node (ref "A11") (pin "F1") (pinfunction "L3_F1") (pintype "bidirectional"))
    )
    (net (code "128") (name "unconnected-(A11B-R1-PadF2)") (class "Default")
      (node (ref "A11") (pin "F2") (pinfunction "R1_F2") (pintype "bidirectional"))
    )
    (net (code "129") (name "unconnected-(A11B-R2-PadH2)") (class "Default")
      (node (ref "A11") (pin "H2") (pinfunction "R2_H2") (pintype "bidirectional"))
    )
    (net (code "130") (name "unconnected-(A11C-L1-PadH1)") (class "Default")
      (node (ref "A11") (pin "H1") (pinfunction "L1_H1") (pintype "bidirectional"))
    )
    (net (code "131") (name "unconnected-(A11C-L2-PadJ1)") (class "Default")
      (node (ref "A11") (pin "J1") (pinfunction "L2_J1") (pintype "bidirectional"))
    )
    (net (code "132") (name "unconnected-(A11C-R1-PadJ2)") (class "Default")
      (node (ref "A11") (pin "J2") (pinfunction "R1_J2") (pintype "bidirectional"))
    )
    (net (code "133") (name "unconnected-(A11C-R2-PadK2)") (class "Default")
      (node (ref "A11") (pin "K2") (pinfunction "R2_K2") (pintype "bidirectional"))
    )
    (net (code "134") (name "unconnected-(A11D-L2-PadM1)") (class "Default")
      (node (ref "A11") (pin "M1") (pinfunction "L2_M1") (pintype "bidirectional"))
    )
    (net (code "135") (name "unconnected-(A11D-L3-PadN1)") (class "Default")
      (node (ref "A11") (pin "N1") (pinfunction "L3_N1") (pintype "bidirectional"))
    )
    (net (code "136") (name "unconnected-(A11D-R2-PadM2)") (class "Default")
      (node (ref "A11") (pin "M2") (pinfunction "R2_M2") (pintype "bidirectional"))
    )
    (net (code "137") (name "unconnected-(A11E-R1-PadN2)") (class "Default")
      (node (ref "A11") (pin "N2") (pinfunction "R1_N2") (pintype "bidirectional"))
    )
    (net (code "138") (name "unconnected-(A11E-R2-PadP2)") (class "Default")
      (node (ref "A11") (pin "P2") (pinfunction "R2_P2") (pintype "bidirectional"))
    )
    (net (code "139") (name "unconnected-(A11F-L1-PadS2)") (class "Default")
      (node (ref "A11") (pin "S2") (pinfunction "L1_S2") (pintype "bidirectional"))
    )
    (net (code "140") (name "unconnected-(A11F-L2-PadU1)") (class "Default")
      (node (ref "A11") (pin "U1") (pinfunction "L2_U1") (pintype "bidirectional"))
    )
    (net (code "141") (name "unconnected-(B04-PadA1)") (class "Default")
      (node (ref "B04") (pin "A1") (pinfunction "A1_A1") (pintype "output"))
    )
    (net (code "142") (name "unconnected-(B04-PadC1)") (class "Default")
      (node (ref "B04") (pin "C1") (pinfunction "C1_C1") (pintype "output"))
    )
    (net (code "143") (name "unconnected-(B04-PadE1)") (class "Default")
      (node (ref "B04") (pin "E1") (pinfunction "E1_E1") (pintype "output"))
    )
    (net (code "144") (name "unconnected-(B04-PadV2)") (class "Default")
      (node (ref "B04") (pin "V2") (pinfunction "V2_V2") (pintype "output"))
    )
    (net (code "145") (name "unconnected-(B05-PadA1)") (class "Default")
      (node (ref "B05") (pin "A1") (pinfunction "A1_A1") (pintype "output"))
    )
    (net (code "146") (name "unconnected-(B05-PadC1)") (class "Default")
      (node (ref "B05") (pin "C1") (pinfunction "C1_C1") (pintype "output"))
    )
    (net (code "147") (name "unconnected-(B05-PadE1)") (class "Default")
      (node (ref "B05") (pin "E1") (pinfunction "E1_E1") (pintype "output"))
    )
    (net (code "148") (name "unconnected-(B05-PadV2)") (class "Default")
      (node (ref "B05") (pin "V2") (pinfunction "V2_V2") (pintype "output"))
    )
    (net (code "149") (name "unconnected-(B10-PadA1)") (class "Default")
      (node (ref "B10") (pin "A1") (pinfunction "A1_A1") (pintype "output"))
    )
    (net (code "150") (name "unconnected-(B10-PadB1)") (class "Default")
      (node (ref "B10") (pin "B1") (pinfunction "B1_B1") (pintype "output"))
    )
    (net (code "151") (name "unconnected-(B10-PadC1)") (class "Default")
      (node (ref "B10") (pin "C1") (pinfunction "C1_C1") (pintype "output"))
    )
    (net (code "152") (name "unconnected-(B10-PadD1)") (class "Default")
      (node (ref "B10") (pin "D1") (pinfunction "D1_D1") (pintype "output"))
    )
    (net (code "153") (name "unconnected-(B10-PadF1)") (class "Default")
      (node (ref "B10") (pin "F1") (pinfunction "F1_F1") (pintype "output"))
    )
    (net (code "154") (name "unconnected-(B10-PadV2)") (class "Default")
      (node (ref "B10") (pin "V2") (pinfunction "V2_V2") (pintype "output"))
    )
    (net (code "155") (name "unconnected-(B11A-L-PadL2)") (class "Default")
      (node (ref "B11") (pin "L2") (pinfunction "L_L2") (pintype "passive"))
    )
    (net (code "156") (name "unconnected-(B11A-M-PadM2)") (class "Default")
      (node (ref "B11") (pin "M2") (pinfunction "M_M2") (pintype "passive"))
    )
    (net (code "157") (name "unconnected-(B11A-T-PadT2)") (class "Default")
      (node (ref "B11") (pin "T2") (pinfunction "T_T2") (pintype "output"))
    )
    (net (code "158") (name "unconnected-(B12A-L-PadL2)") (class "Default")
      (node (ref "B12") (pin "L2") (pinfunction "L_L2") (pintype "passive"))
    )
    (net (code "159") (name "unconnected-(B12A-M-PadM2)") (class "Default")
      (node (ref "B12") (pin "M2") (pinfunction "M_M2") (pintype "passive"))
    )
    (net (code "160") (name "unconnected-(B12A-S-PadS2)") (class "Default")
      (node (ref "B12") (pin "S2") (pinfunction "S_S2") (pintype "output"))
    )
  )
)
